# Sheet3.net
KiCad netlist of a schematic drawn in Altium Designer
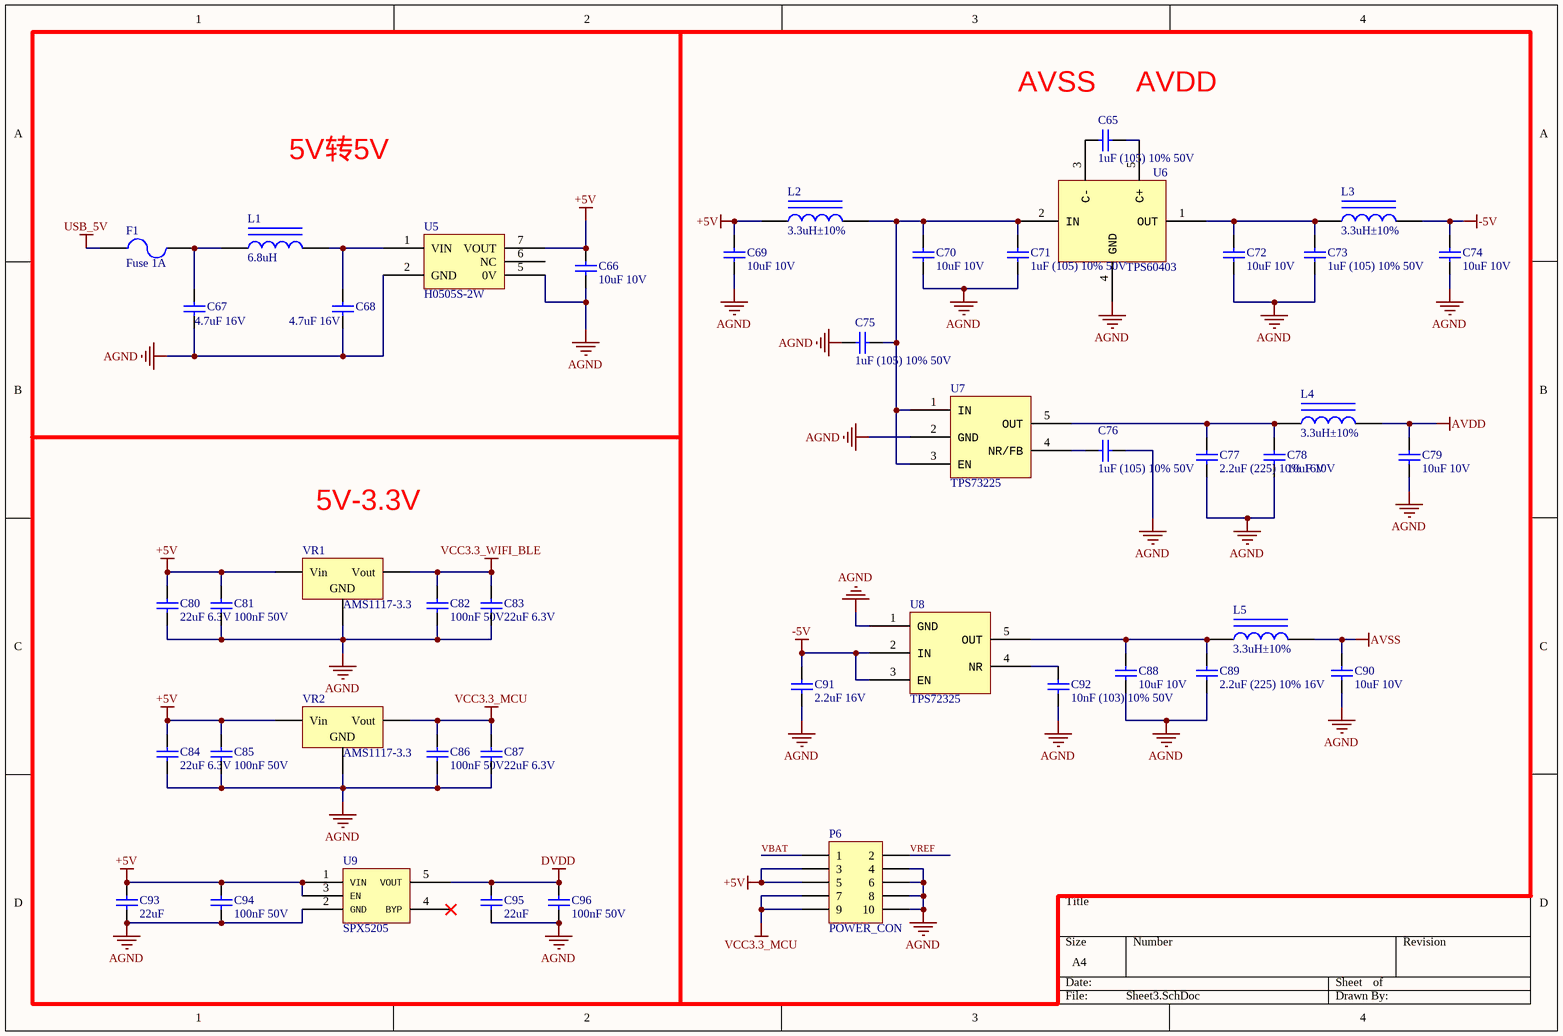
[diagram p0: Sheet3.SchDoc]

(export (version "E")
  (design (tool "Eeschema 10.0.6"))
  (components
    (comp (ref "C65")
      (value "1uF (105) 10% 50V")
      (footprint "0603_C")
      (description "贴片电容")
      (libsource (lib "Miscellaneous Devices LC") (part "0603 1uF (105) 10% 50V"))
    )
    (comp (ref "C66")
      (value "10uF 10V")
      (footprint "0603_C")
      (description "贴片电容")
      (libsource (lib "Miscellaneous Devices LC") (part "0603 10uF (106) 10% 10V"))
    )
    (comp (ref "C67")
      (value "4.7uF 16V")
      (footprint "0603_C")
      (description "贴片电容")
      (libsource (lib "Miscellaneous Devices LC") (part "0603 4.7uF (475) 10% 16V"))
    )
    (comp (ref "C68")
      (value "4.7uF 16V")
      (footprint "0603_C")
      (description "贴片电容")
      (libsource (lib "Miscellaneous Devices LC") (part "0603 4.7uF (475) 10% 16V"))
    )
    (comp (ref "C69")
      (value "10uF 10V")
      (footprint "0603_C")
      (description "贴片电容")
      (libsource (lib "Miscellaneous Devices LC") (part "0603 10uF (106) 10% 10V"))
    )
    (comp (ref "C70")
      (value "10uF 10V")
      (footprint "0603_C")
      (description "贴片电容")
      (libsource (lib "Miscellaneous Devices LC") (part "0603 10uF (106) 10% 10V"))
    )
    (comp (ref "C71")
      (value "1uF (105) 10% 50V")
      (footprint "0603_C")
      (description "贴片电容")
      (libsource (lib "Miscellaneous Devices LC") (part "0603 1uF (105) 10% 50V"))
    )
    (comp (ref "C72")
      (value "10uF 10V")
      (footprint "0603_C")
      (description "贴片电容")
      (libsource (lib "Miscellaneous Devices LC") (part "0603 10uF (106) 10% 10V"))
    )
    (comp (ref "C73")
      (value "1uF (105) 10% 50V")
      (footprint "0603_C")
      (description "贴片电容")
      (libsource (lib "Miscellaneous Devices LC") (part "0603 1uF (105) 10% 50V"))
    )
    (comp (ref "C74")
      (value "10uF 10V")
      (footprint "0603_C")
      (description "贴片电容")
      (libsource (lib "Miscellaneous Devices LC") (part "0603 10uF (106) 10% 10V"))
    )
    (comp (ref "C75")
      (value "1uF (105) 10% 50V")
      (footprint "0603_C")
      (description "贴片电容")
      (libsource (lib "Miscellaneous Devices LC") (part "0603 1uF (105) 10% 50V"))
    )
    (comp (ref "C76")
      (value "1uF (105) 10% 50V")
      (footprint "0603_C")
      (description "贴片电容")
      (libsource (lib "Miscellaneous Devices LC") (part "0603 1uF (105) 10% 50V"))
    )
    (comp (ref "C77")
      (value "2.2uF (225) 10% 16V")
      (footprint "0603_C")
      (description "贴片电容")
      (libsource (lib "Miscellaneous Devices LC") (part "0603 2.2uF (225) 10% 16V"))
    )
    (comp (ref "C78")
      (value "10uF 10V")
      (footprint "0603_C")
      (description "贴片电容")
      (libsource (lib "Miscellaneous Devices LC") (part "0603 10uF (106) 10% 10V"))
    )
    (comp (ref "C79")
      (value "10uF 10V")
      (footprint "0603_C")
      (description "贴片电容")
      (libsource (lib "Miscellaneous Devices LC") (part "0603 10uF (106) 10% 10V"))
    )
    (comp (ref "C80")
      (value "22uF 6.3V")
      (footprint "0603_C")
      (description "贴片电容")
      (libsource (lib "Miscellaneous Devices LC") (part "0603 22uF (226) 20% 6.3V"))
    )
    (comp (ref "C81")
      (value "100nF 50V")
      (footprint "0603_C")
      (description "贴片电容")
      (libsource (lib "Miscellaneous Devices LC") (part "0603 100nF (104) 10% 50V"))
    )
    (comp (ref "C82")
      (value "100nF 50V")
      (footprint "0603_C")
      (description "贴片电容")
      (libsource (lib "Miscellaneous Devices LC") (part "0603 100nF (104) 10% 50V"))
    )
    (comp (ref "C83")
      (value "22uF 6.3V")
      (footprint "0603_C")
      (description "贴片电容")
      (libsource (lib "Miscellaneous Devices LC") (part "0603 22uF (226) 20% 6.3V"))
    )
    (comp (ref "C84")
      (value "22uF 6.3V")
      (footprint "0603_C")
      (description "贴片电容")
      (libsource (lib "Miscellaneous Devices LC") (part "0603 22uF (226) 20% 6.3V"))
    )
    (comp (ref "C85")
      (value "100nF 50V")
      (footprint "0603_C")
      (description "贴片电容")
      (libsource (lib "Miscellaneous Devices LC") (part "0603 100nF (104) 10% 50V"))
    )
    (comp (ref "C86")
      (value "100nF 50V")
      (footprint "0603_C")
      (description "贴片电容")
      (libsource (lib "Miscellaneous Devices LC") (part "0603 100nF (104) 10% 50V"))
    )
    (comp (ref "C87")
      (value "22uF 6.3V")
      (footprint "0603_C")
      (description "贴片电容")
      (libsource (lib "Miscellaneous Devices LC") (part "0603 22uF (226) 20% 6.3V"))
    )
    (comp (ref "C88")
      (value "10uF 10V")
      (footprint "0603_C")
      (description "贴片电容")
      (libsource (lib "Miscellaneous Devices LC") (part "0603 10uF (106) 10% 10V"))
    )
    (comp (ref "C89")
      (value "2.2uF (225) 10% 16V")
      (footprint "0603_C")
      (description "贴片电容")
      (libsource (lib "Miscellaneous Devices LC") (part "0603 2.2uF (225) 10% 16V"))
    )
    (comp (ref "C90")
      (value "10uF 10V")
      (footprint "0603_C")
      (description "贴片电容")
      (libsource (lib "Miscellaneous Devices LC") (part "0603 10uF (106) 10% 10V"))
    )
    (comp (ref "C91")
      (value "2.2uF 16V")
      (footprint "0603_C")
      (description "贴片电容")
      (libsource (lib "Miscellaneous Devices LC") (part "0603 2.2uF (225) 10% 16V"))
    )
    (comp (ref "C92")
      (value "10nF (103) 10% 50V")
      (footprint "0603_C")
      (description "贴片电容")
      (libsource (lib "Miscellaneous Devices LC") (part "0603 10nF (103) 10% 50V"))
    )
    (comp (ref "C93")
      (value "22uF")
      (footprint "0603_C")
      (description "贴片电容")
      (libsource (lib "Miscellaneous Devices LC") (part "0603 22uF (226) 20% 6.3V"))
    )
    (comp (ref "C94")
      (value "100nF 50V")
      (footprint "0603_C")
      (description "贴片电容")
      (libsource (lib "Miscellaneous Devices LC") (part "0603 100nF (104) 10% 50V"))
    )
    (comp (ref "C95")
      (value "22uF")
      (footprint "0603_C")
      (description "贴片电容")
      (libsource (lib "Miscellaneous Devices LC") (part "0603 22uF (226) 20% 6.3V"))
    )
    (comp (ref "C96")
      (value "100nF 50V")
      (footprint "0603_C")
      (description "贴片电容")
      (libsource (lib "Miscellaneous Devices LC") (part "0603 100nF (104) 10% 50V"))
    )
    (comp (ref "F1")
      (value "Fuse 1A")
      (footprint "0805_R")
      (description "Fuse")
      (fields (field (name "PUBLISHER") "Altium Limited"))
      (libsource (lib "Miscellaneous Devices") (part "Fuse 2"))
    )
    (comp (ref "L1")
      (value "6.8uH")
      (footprint "0603_L")
      (description "贴片电感")
      (libsource (lib "Miscellaneous Devices LC") (part "0603 4.7uH 10%"))
    )
    (comp (ref "L2")
      (value "3.3uH±10%")
      (footprint "0805_L")
      (description "贴片电感")
      (libsource (lib "Miscellaneous Devices LC") (part "0805 3.3uH10%"))
    )
    (comp (ref "L3")
      (value "3.3uH±10%")
      (footprint "0805_L")
      (description "贴片电感")
      (libsource (lib "Miscellaneous Devices LC") (part "0805 3.3uH10%"))
    )
    (comp (ref "L4")
      (value "3.3uH±10%")
      (footprint "0805_L")
      (description "贴片电感")
      (libsource (lib "Miscellaneous Devices LC") (part "0805 3.3uH10%"))
    )
    (comp (ref "L5")
      (value "3.3uH±10%")
      (footprint "0805_L")
      (description "贴片电感")
      (libsource (lib "Miscellaneous Devices LC") (part "0805 3.3uH10%"))
    )
    (comp (ref "P6")
      (value "POWER_CON")
      (footprint "HDR2X5")
      (description "Header, 5-Pin, Dual row")
      (fields (field (name "PUBLISHER") "Altium Limited"))
      (libsource (lib "Miscellaneous Connectors") (part "Header 5X2"))
    )
    (comp (ref "U5") (value "H0505S-2W") (footprint "H0505S") (libsource (lib "EEG") (part "H0505S-2W")))
    (comp (ref "U6") (value "TPS60403") (footprint "SOT-23-5") (libsource (lib "ads1299") (part "TPS60403")))
    (comp (ref "U7") (value "TPS73225") (footprint "SOT-23-5") (libsource (lib "ads1299") (part "TPS73225")))
    (comp (ref "U8") (value "TPS72325") (footprint "SOT-23-5") (libsource (lib "ads1299") (part "TPS72325")))
    (comp (ref "U9") (value "SPX5205") (footprint "SOT-23-5") (libsource (lib "EEG") (part "SPX5205")))
    (comp (ref "VR1")
      (value "AMS1117-3.3")
      (footprint "SOT-223")
      (description "低压差线性稳压(LDO)")
      (libsource (lib "Miscellaneous Devices LC") (part "SOT-223 AMS1117-3.3"))
    )
    (comp (ref "VR2")
      (value "AMS1117-3.3")
      (footprint "SOT-223")
      (description "低压差线性稳压(LDO)")
      (libsource (lib "Miscellaneous Devices LC") (part "SOT-223 AMS1117-3.3"))
    )
  )
  (nets
    (net (code "1") (name "+5V") (class "Default")
      (node (ref "C66") (pin "2") (pinfunction "2_2") (pintype "passive"))
      (node (ref "C69") (pin "2") (pinfunction "2_2") (pintype "passive"))
      (node (ref "C80") (pin "2") (pinfunction "2_2") (pintype "passive"))
      (node (ref "C81") (pin "2") (pinfunction "2_2") (pintype "passive"))
      (node (ref "C84") (pin "2") (pinfunction "2_2") (pintype "passive"))
      (node (ref "C85") (pin "2") (pinfunction "2_2") (pintype "passive"))
      (node (ref "C93") (pin "2") (pinfunction "2_2") (pintype "passive"))
      (node (ref "C94") (pin "2") (pinfunction "2_2") (pintype "passive"))
      (node (ref "L2") (pin "1") (pinfunction "1_1") (pintype "passive"))
      (node (ref "P6") (pin "3") (pinfunction "3_3") (pintype "passive"))
      (node (ref "P6") (pin "5") (pinfunction "5_5") (pintype "passive"))
      (node (ref "U5") (pin "7") (pinfunction "VOUT_7") (pintype "passive"))
      (node (ref "U9") (pin "1") (pinfunction "VIN_1") (pintype "passive"))
      (node (ref "U9") (pin "3") (pinfunction "EN_3") (pintype "passive"))
      (node (ref "VR1") (pin "3") (pinfunction "Vin_3") (pintype "passive"))
      (node (ref "VR2") (pin "3") (pinfunction "Vin_3") (pintype "passive"))
    )
    (net (code "2") (name "-5V") (class "Default")
      (node (ref "C74") (pin "2") (pinfunction "2_2") (pintype "passive"))
      (node (ref "C91") (pin "2") (pinfunction "2_2") (pintype "passive"))
      (node (ref "L3") (pin "2") (pinfunction "2_2") (pintype "passive"))
      (node (ref "U8") (pin "2") (pinfunction "IN_2") (pintype "passive"))
      (node (ref "U8") (pin "3") (pinfunction "EN_3") (pintype "passive"))
    )
    (net (code "3") (name "/VBAT") (class "Default")
      (node (ref "P6") (pin "1") (pinfunction "1_1") (pintype "passive"))
    )
    (net (code "4") (name "/VREF") (class "Default")
      (node (ref "P6") (pin "2") (pinfunction "2_2") (pintype "passive"))
    )
    (net (code "5") (name "AGND") (class "Default")
      (node (ref "C66") (pin "1") (pinfunction "1_1") (pintype "passive"))
      (node (ref "C67") (pin "1") (pinfunction "1_1") (pintype "passive"))
      (node (ref "C68") (pin "1") (pinfunction "1_1") (pintype "passive"))
      (node (ref "C69") (pin "1") (pinfunction "1_1") (pintype "passive"))
      (node (ref "C70") (pin "1") (pinfunction "1_1") (pintype "passive"))
      (node (ref "C71") (pin "1") (pinfunction "1_1") (pintype "passive"))
      (node (ref "C72") (pin "1") (pinfunction "1_1") (pintype "passive"))
      (node (ref "C73") (pin "1") (pinfunction "1_1") (pintype "passive"))
      (node (ref "C74") (pin "1") (pinfunction "1_1") (pintype "passive"))
      (node (ref "C75") (pin "2") (pinfunction "2_2") (pintype "passive"))
      (node (ref "C76") (pin "1") (pinfunction "1_1") (pintype "passive"))
      (node (ref "C77") (pin "1") (pinfunction "1_1") (pintype "passive"))
      (node (ref "C78") (pin "1") (pinfunction "1_1") (pintype "passive"))
      (node (ref "C79") (pin "1") (pinfunction "1_1") (pintype "passive"))
      (node (ref "C80") (pin "1") (pinfunction "1_1") (pintype "passive"))
      (node (ref "C81") (pin "1") (pinfunction "1_1") (pintype "passive"))
      (node (ref "C82") (pin "1") (pinfunction "1_1") (pintype "passive"))
      (node (ref "C83") (pin "1") (pinfunction "1_1") (pintype "passive"))
      (node (ref "C84") (pin "1") (pinfunction "1_1") (pintype "passive"))
      (node (ref "C85") (pin "1") (pinfunction "1_1") (pintype "passive"))
      (node (ref "C86") (pin "1") (pinfunction "1_1") (pintype "passive"))
      (node (ref "C87") (pin "1") (pinfunction "1_1") (pintype "passive"))
      (node (ref "C88") (pin "1") (pinfunction "1_1") (pintype "passive"))
      (node (ref "C89") (pin "1") (pinfunction "1_1") (pintype "passive"))
      (node (ref "C90") (pin "1") (pinfunction "1_1") (pintype "passive"))
      (node (ref "C91") (pin "1") (pinfunction "1_1") (pintype "passive"))
      (node (ref "C92") (pin "1") (pinfunction "1_1") (pintype "passive"))
      (node (ref "C93") (pin "1") (pinfunction "1_1") (pintype "passive"))
      (node (ref "C94") (pin "1") (pinfunction "1_1") (pintype "passive"))
      (node (ref "C95") (pin "1") (pinfunction "1_1") (pintype "passive"))
      (node (ref "C96") (pin "1") (pinfunction "1_1") (pintype "passive"))
      (node (ref "P6") (pin "10") (pinfunction "10_10") (pintype "passive"))
      (node (ref "P6") (pin "4") (pinfunction "4_4") (pintype "passive"))
      (node (ref "P6") (pin "6") (pinfunction "6_6") (pintype "passive"))
      (node (ref "P6") (pin "8") (pinfunction "8_8") (pintype "passive"))
      (node (ref "U5") (pin "2") (pinfunction "GND_2") (pintype "passive"))
      (node (ref "U5") (pin "5") (pinfunction "0V_5") (pintype "passive"))
      (node (ref "U6") (pin "4") (pinfunction "GND_4") (pintype "passive"))
      (node (ref "U7") (pin "2") (pinfunction "GND_2") (pintype "passive"))
      (node (ref "U8") (pin "1") (pinfunction "GND_1") (pintype "passive"))
      (node (ref "U9") (pin "2") (pinfunction "GND_2") (pintype "passive"))
      (node (ref "VR1") (pin "1") (pinfunction "GND_1") (pintype "passive"))
      (node (ref "VR2") (pin "1") (pinfunction "GND_1") (pintype "passive"))
    )
    (net (code "6") (name "AVDD") (class "Default")
      (node (ref "C79") (pin "2") (pinfunction "2_2") (pintype "passive"))
      (node (ref "L4") (pin "2") (pinfunction "2_2") (pintype "passive"))
    )
    (net (code "7") (name "AVSS") (class "Default")
      (node (ref "C90") (pin "2") (pinfunction "2_2") (pintype "passive"))
      (node (ref "L5") (pin "2") (pinfunction "2_2") (pintype "passive"))
    )
    (net (code "8") (name "DVDD") (class "Default")
      (node (ref "C95") (pin "2") (pinfunction "2_2") (pintype "passive"))
      (node (ref "C96") (pin "2") (pinfunction "2_2") (pintype "passive"))
      (node (ref "U9") (pin "5") (pinfunction "VOUT_5") (pintype "passive"))
    )
    (net (code "9") (name "Net-(C67-Pad2)") (class "Default")
      (node (ref "C67") (pin "2") (pinfunction "2_2") (pintype "passive"))
      (node (ref "F1") (pin "2") (pinfunction "2_2") (pintype "passive"))
      (node (ref "L1") (pin "1") (pinfunction "1_1") (pintype "passive"))
    )
    (net (code "10") (name "Net-(U5-VIN)") (class "Default")
      (node (ref "C68") (pin "2") (pinfunction "2_2") (pintype "passive"))
      (node (ref "L1") (pin "2") (pinfunction "2_2") (pintype "passive"))
      (node (ref "U5") (pin "1") (pinfunction "VIN_1") (pintype "passive"))
    )
    (net (code "11") (name "Net-(U6-C+)") (class "Default")
      (node (ref "C65") (pin "1") (pinfunction "1_1") (pintype "passive"))
      (node (ref "U6") (pin "5") (pinfunction "C+_5") (pintype "passive"))
    )
    (net (code "12") (name "Net-(U6-C-)") (class "Default")
      (node (ref "C65") (pin "2") (pinfunction "2_2") (pintype "passive"))
      (node (ref "U6") (pin "3") (pinfunction "C-_3") (pintype "passive"))
    )
    (net (code "13") (name "Net-(U6-IN)") (class "Default")
      (node (ref "C70") (pin "2") (pinfunction "2_2") (pintype "passive"))
      (node (ref "C71") (pin "2") (pinfunction "2_2") (pintype "passive"))
      (node (ref "C75") (pin "1") (pinfunction "1_1") (pintype "passive"))
      (node (ref "L2") (pin "2") (pinfunction "2_2") (pintype "passive"))
      (node (ref "U6") (pin "2") (pinfunction "IN_2") (pintype "passive"))
      (node (ref "U7") (pin "1") (pinfunction "IN_1") (pintype "passive"))
      (node (ref "U7") (pin "3") (pinfunction "EN_3") (pintype "passive"))
    )
    (net (code "14") (name "Net-(U6-OUT)") (class "Default")
      (node (ref "C72") (pin "2") (pinfunction "2_2") (pintype "passive"))
      (node (ref "C73") (pin "2") (pinfunction "2_2") (pintype "passive"))
      (node (ref "L3") (pin "1") (pinfunction "1_1") (pintype "passive"))
      (node (ref "U6") (pin "1") (pinfunction "OUT_1") (pintype "passive"))
    )
    (net (code "15") (name "Net-(U7-NR{slash}FB)") (class "Default")
      (node (ref "C76") (pin "2") (pinfunction "2_2") (pintype "passive"))
      (node (ref "U7") (pin "4") (pinfunction "NR/FB_4") (pintype "passive"))
    )
    (net (code "16") (name "Net-(U7-OUT)") (class "Default")
      (node (ref "C77") (pin "2") (pinfunction "2_2") (pintype "passive"))
      (node (ref "C78") (pin "2") (pinfunction "2_2") (pintype "passive"))
      (node (ref "L4") (pin "1") (pinfunction "1_1") (pintype "passive"))
      (node (ref "U7") (pin "5") (pinfunction "OUT_5") (pintype "passive"))
    )
    (net (code "17") (name "Net-(U8-NR)") (class "Default")
      (node (ref "C92") (pin "2") (pinfunction "2_2") (pintype "passive"))
      (node (ref "U8") (pin "4") (pinfunction "NR_4") (pintype "passive"))
    )
    (net (code "18") (name "Net-(U8-OUT)") (class "Default")
      (node (ref "C88") (pin "2") (pinfunction "2_2") (pintype "passive"))
      (node (ref "C89") (pin "2") (pinfunction "2_2") (pintype "passive"))
      (node (ref "L5") (pin "1") (pinfunction "1_1") (pintype "passive"))
      (node (ref "U8") (pin "5") (pinfunction "OUT_5") (pintype "passive"))
    )
    (net (code "19") (name "USB_5V") (class "Default")
      (node (ref "F1") (pin "1") (pinfunction "1_1") (pintype "passive"))
    )
    (net (code "20") (name "VCC3.3_MCU") (class "Default")
      (node (ref "C86") (pin "2") (pinfunction "2_2") (pintype "passive"))
      (node (ref "C87") (pin "2") (pinfunction "2_2") (pintype "passive"))
      (node (ref "P6") (pin "7") (pinfunction "7_7") (pintype "passive"))
      (node (ref "P6") (pin "9") (pinfunction "9_9") (pintype "passive"))
      (node (ref "VR2") (pin "2") (pinfunction "Vout_2") (pintype "passive"))
    )
    (net (code "21") (name "VCC3.3_WIFI_BLE") (class "Default")
      (node (ref "C82") (pin "2") (pinfunction "2_2") (pintype "passive"))
      (node (ref "C83") (pin "2") (pinfunction "2_2") (pintype "passive"))
      (node (ref "VR1") (pin "2") (pinfunction "Vout_2") (pintype "passive"))
    )
    (net (code "22") (name "unconnected-(U5-NC-Pad6)") (class "Default")
      (node (ref "U5") (pin "6") (pinfunction "NC_6") (pintype "passive"))
    )
    (net (code "23") (name "unconnected-(U9-BYP-Pad4)") (class "Default")
      (node (ref "U9") (pin "4") (pinfunction "BYP_4") (pintype "passive+no_connect"))
    )
  )
)
